# Sheet1.net
KiCad netlist of a schematic drawn in Altium Designer
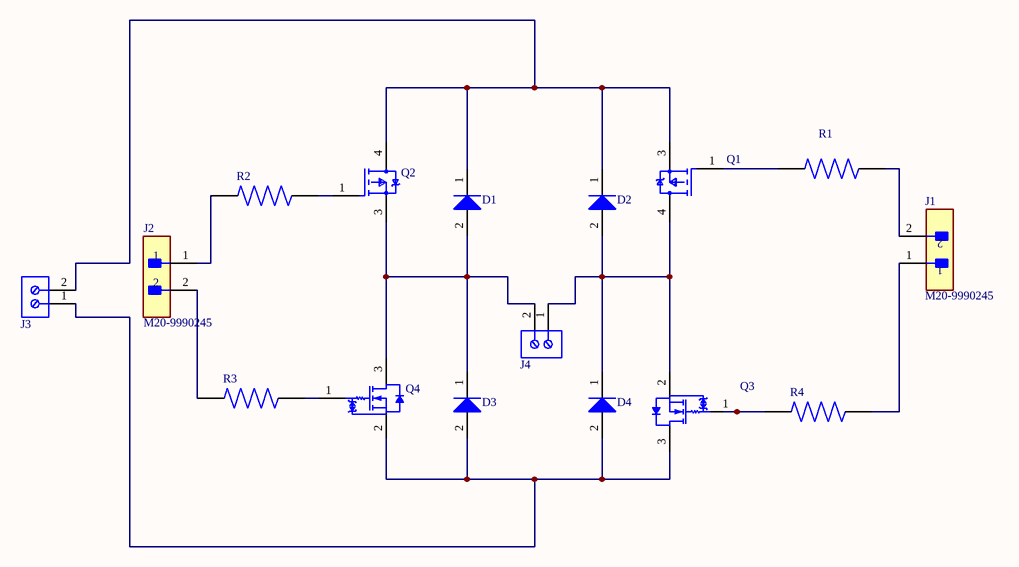
[diagram p0: Sheet1.SchDoc]

(export (version "E")
  (design (tool "Eeschema 10.0.6"))
  (components
    (comp (ref "D1")
      (value "BAT54HT1G")
      (footprint "ONSC-SOD-323-2-477-02_V")
      (description "Schottky Barrier Diode, 2-Pin SOD-323, Pb-Free, Tape and Reel")
      (fields (field (name "MANUFACTURER") "On Semiconductor"))
      (libsource (lib "Altium Content Vault") (part "ONSC-D-K1A2-2"))
    )
    (comp (ref "D2")
      (value "BAT54HT1G")
      (footprint "ONSC-SOD-323-2-477-02_V")
      (description "Schottky Barrier Diode, 2-Pin SOD-323, Pb-Free, Tape and Reel")
      (fields (field (name "MANUFACTURER") "On Semiconductor"))
      (libsource (lib "Altium Content Vault") (part "ONSC-D-K1A2-2"))
    )
    (comp (ref "D3")
      (value "BAT54HT1G")
      (footprint "ONSC-SOD-323-2-477-02_V")
      (description "Schottky Barrier Diode, 2-Pin SOD-323, Pb-Free, Tape and Reel")
      (fields (field (name "MANUFACTURER") "On Semiconductor"))
      (libsource (lib "Altium Content Vault") (part "ONSC-D-K1A2-2"))
    )
    (comp (ref "D4")
      (value "BAT54HT1G")
      (footprint "ONSC-SOD-323-2-477-02_V")
      (description "Schottky Barrier Diode, 2-Pin SOD-323, Pb-Free, Tape and Reel")
      (fields (field (name "MANUFACTURER") "On Semiconductor"))
      (libsource (lib "Altium Content Vault") (part "ONSC-D-K1A2-2"))
    )
    (comp (ref "J1")
      (value "M20-9990245")
      (footprint "FP-M20-9990245-MFG")
      (description "CONN HEADER VERT 2POS 2.54MM")
      (fields (field (name "VOLTAGE") "50V"))
      (libsource (lib "") (part "3bc925449376181038e59eaffc5286c_1"))
    )
    (comp (ref "J2")
      (value "M20-9990245")
      (footprint "FP-M20-9990245-MFG")
      (description "CONN HEADER VERT 2POS 2.54MM")
      (fields (field (name "VOLTAGE") "50V"))
      (libsource (lib "Altium Content Vault") (part "3bc925449376181038e59eaffc5286c"))
    )
    (comp (ref "J3")
      (value "691214110002")
      (footprint "691214110002")
      (fields (field (name "VOLTAGE") "300V"))
      (libsource (lib "Altium Content Vault") (part "TBL - 1R - 02P - Screw"))
    )
    (comp (ref "J4")
      (value "691214110002")
      (footprint "691214110002")
      (fields (field (name "VOLTAGE") "300V"))
      (libsource (lib "Altium Content Vault") (part "TBL - 1R - 02P - Screw"))
    )
    (comp (ref "Q1")
      (value "NTB25P06T4G")
      (footprint "FP-418B-04-MFG")
      (libsource (lib "Altium Content Vault") (part "198104cda15d533ba7643ca1a8c9fd7"))
    )
    (comp (ref "Q2")
      (value "NTB25P06T4G")
      (footprint "FP-418B-04-MFG")
      (libsource (lib "Altium Content Vault") (part "198104cda15d533ba7643ca1a8c9fd7"))
    )
    (comp (ref "Q3")
      (value "2N7002WT1G")
      (footprint "ONSC-SC-70-3-419-04_V")
      (description "Small Signal MOSFET, 60 V, 340 mA, Single, N-Channel, 3-Pin SC70, Pb-Free, Tape and Reel")
      (fields (field (name "MANUFACTURER") "On Semiconductor"))
      (libsource (lib "Altium Content Vault") (part "ONSC-NMOS-G1S2D3-3_C"))
    )
    (comp (ref "Q4")
      (value "2N7002WT1G")
      (footprint "ONSC-SC-70-3-419-04_V")
      (description "Small Signal MOSFET, 60 V, 340 mA, Single, N-Channel, 3-Pin SC70, Pb-Free, Tape and Reel")
      (fields (field (name "MANUFACTURER") "On Semiconductor"))
      (libsource (lib "Altium Content Vault") (part "ONSC-NMOS-G1S2D3-3_C"))
    )
    (comp (ref "R1")
      (value "RNC55H3300BSRE6")
      (footprint "RESAD1081W64L635D269")
      (fields (field (name "MF") "Vishay"))
      (libsource (lib "RNC55H3300BSRE6") (part "RNC55H3300BSRE6"))
    )
    (comp (ref "R2")
      (value "RNC55H3300BSRE6")
      (footprint "RESAD1081W64L635D269")
      (fields (field (name "MF") "Vishay"))
      (libsource (lib "RNC55H3300BSRE6") (part "RNC55H3300BSRE6"))
    )
    (comp (ref "R3")
      (value "RNC55H3300BSRE6")
      (footprint "RESAD1081W64L635D269")
      (fields (field (name "MF") "Vishay"))
      (libsource (lib "RNC55H3300BSRE6") (part "RNC55H3300BSRE6"))
    )
    (comp (ref "R4")
      (value "RNC55H3300BSRE6")
      (footprint "RESAD1081W64L635D269")
      (fields (field (name "MF") "Vishay"))
      (libsource (lib "RNC55H3300BSRE6") (part "RNC55H3300BSRE6"))
    )
  )
  (nets
    (net (code "1") (name "Net-(D1-A)") (class "Default")
      (node (ref "D1") (pin "2") (pinfunction "A_2") (pintype "passive"))
      (node (ref "D3") (pin "1") (pinfunction "K_1") (pintype "passive"))
      (node (ref "J4") (pin "2") (pinfunction "2_2") (pintype "passive"))
      (node (ref "Q2") (pin "3") (pinfunction "S_3") (pintype "passive"))
      (node (ref "Q4") (pin "3") (pinfunction "D_3") (pintype "passive"))
    )
    (net (code "2") (name "Net-(D1-K)") (class "Default")
      (node (ref "D1") (pin "1") (pinfunction "K_1") (pintype "passive"))
      (node (ref "D2") (pin "1") (pinfunction "K_1") (pintype "passive"))
      (node (ref "J3") (pin "2") (pinfunction "2_2") (pintype "passive"))
      (node (ref "Q1") (pin "3") (pinfunction "S_3") (pintype "passive"))
      (node (ref "Q2") (pin "4") (pinfunction "D_4") (pintype "passive"))
    )
    (net (code "3") (name "Net-(D2-A)") (class "Default")
      (node (ref "D2") (pin "2") (pinfunction "A_2") (pintype "passive"))
      (node (ref "D4") (pin "1") (pinfunction "K_1") (pintype "passive"))
      (node (ref "J4") (pin "1") (pinfunction "1_1") (pintype "passive"))
      (node (ref "Q1") (pin "4") (pinfunction "D_4") (pintype "passive"))
      (node (ref "Q3") (pin "2") (pinfunction "S_2") (pintype "passive"))
    )
    (net (code "4") (name "Net-(D3-A)") (class "Default")
      (node (ref "D3") (pin "2") (pinfunction "A_2") (pintype "passive"))
      (node (ref "D4") (pin "2") (pinfunction "A_2") (pintype "passive"))
      (node (ref "J3") (pin "1") (pinfunction "1_1") (pintype "passive"))
      (node (ref "Q3") (pin "3") (pinfunction "D_3") (pintype "passive"))
      (node (ref "Q4") (pin "2") (pinfunction "S_2") (pintype "passive"))
    )
    (net (code "5") (name "Net-(J1-Pad1)") (class "Default")
      (node (ref "J1") (pin "1") (pinfunction "1_1") (pintype "passive"))
      (node (ref "R4") (pin "2") (pinfunction "2_2") (pintype "passive"))
    )
    (net (code "6") (name "Net-(J1-Pad2)") (class "Default")
      (node (ref "J1") (pin "2") (pinfunction "2_2") (pintype "passive"))
      (node (ref "R1") (pin "2") (pinfunction "2_2") (pintype "passive"))
    )
    (net (code "7") (name "Net-(J2-Pad1)") (class "Default")
      (node (ref "J2") (pin "1") (pinfunction "1_1") (pintype "passive"))
      (node (ref "R2") (pin "1") (pinfunction "1_1") (pintype "passive"))
    )
    (net (code "8") (name "Net-(J2-Pad2)") (class "Default")
      (node (ref "J2") (pin "2") (pinfunction "2_2") (pintype "passive"))
      (node (ref "R3") (pin "1") (pinfunction "1_1") (pintype "passive"))
    )
    (net (code "9") (name "Net-(Q1-G)") (class "Default")
      (node (ref "Q1") (pin "1") (pinfunction "G_1") (pintype "passive"))
      (node (ref "R1") (pin "1") (pinfunction "1_1") (pintype "passive"))
    )
    (net (code "10") (name "Net-(Q2-G)") (class "Default")
      (node (ref "Q2") (pin "1") (pinfunction "G_1") (pintype "passive"))
      (node (ref "R2") (pin "2") (pinfunction "2_2") (pintype "passive"))
    )
    (net (code "11") (name "Net-(Q3-G)") (class "Default")
      (node (ref "Q3") (pin "1") (pinfunction "G_1") (pintype "passive"))
      (node (ref "R4") (pin "1") (pinfunction "1_1") (pintype "passive"))
    )
    (net (code "12") (name "Net-(Q4-G)") (class "Default")
      (node (ref "Q4") (pin "1") (pinfunction "G_1") (pintype "passive"))
      (node (ref "R3") (pin "2") (pinfunction "2_2") (pintype "passive"))
    )
  )
)
